# labwiz-module_t420.net
KiCad netlist of a schematic drawn in EAGLE
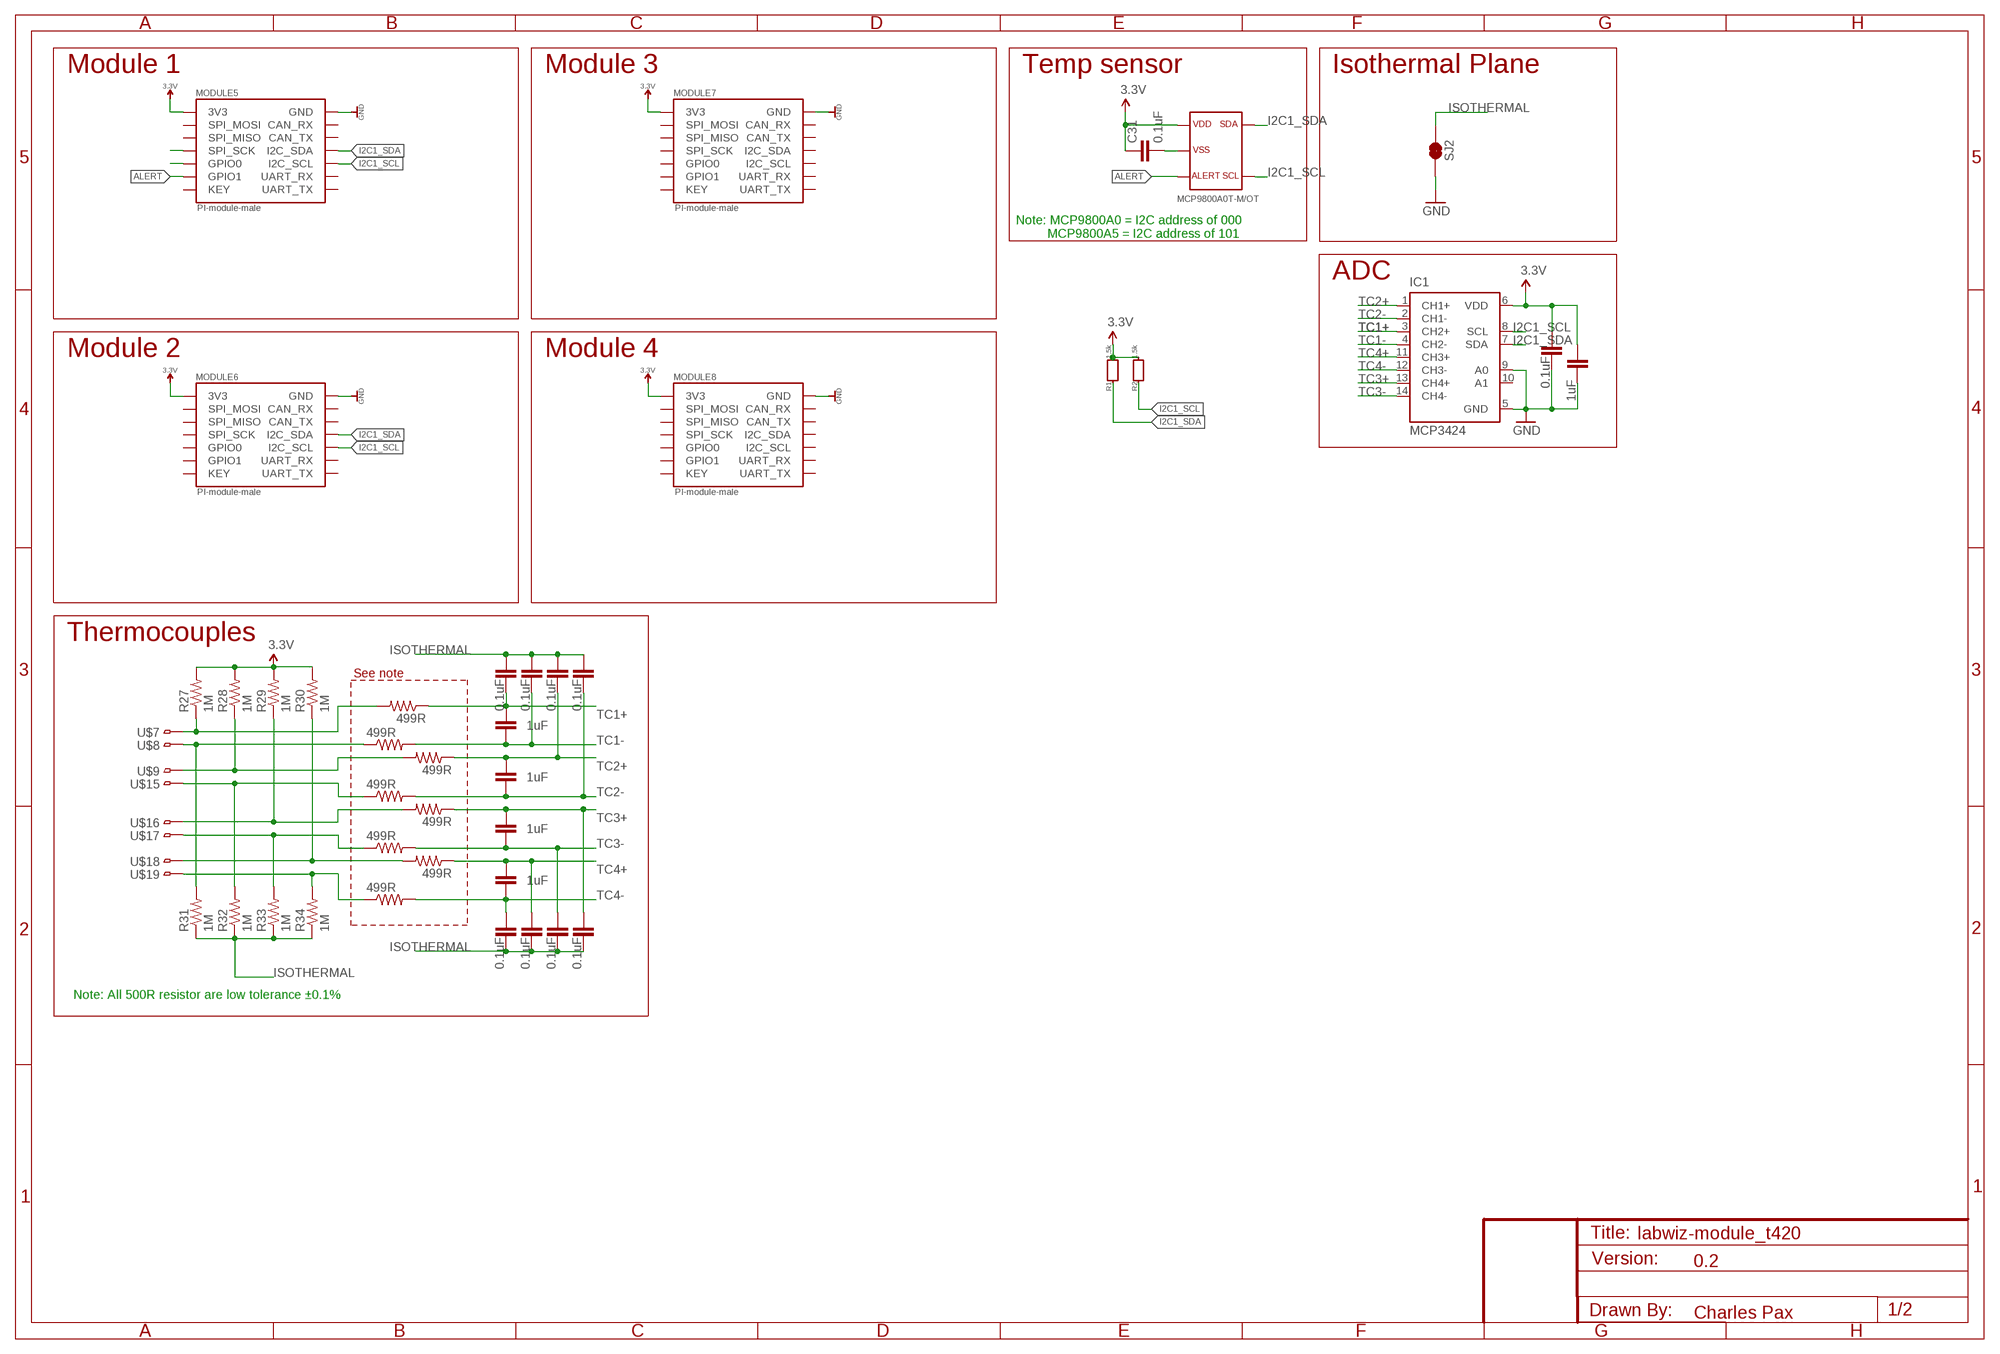
[diagram p0: schematic, sheet 1]

(export (version "E")
  (design (tool "Eeschema 10.0.6"))
  (components
    (comp (ref "C7")
      (value "1uF")
      (footprint "eagle-import:SPARKFUN-CAPACITORS_0603-CAP")
      (libsource (lib "eagle-import") (part "SPARKFUN-CAPACITORS_CAP0603-CAP"))
    )
    (comp (ref "C8")
      (value "1uF")
      (footprint "eagle-import:SPARKFUN-CAPACITORS_0603-CAP")
      (libsource (lib "eagle-import") (part "SPARKFUN-CAPACITORS_CAP0603-CAP"))
    )
    (comp (ref "C10")
      (value "1uF")
      (footprint "eagle-import:SPARKFUN-CAPACITORS_0603-CAP")
      (libsource (lib "eagle-import") (part "SPARKFUN-CAPACITORS_CAP0603-CAP"))
    )
    (comp (ref "C11")
      (value "1uF")
      (footprint "eagle-import:SPARKFUN-CAPACITORS_0603-CAP")
      (libsource (lib "eagle-import") (part "SPARKFUN-CAPACITORS_CAP0603-CAP"))
    )
    (comp (ref "C13")
      (value "0.1uF")
      (footprint "eagle-import:SPARKFUN-CAPACITORS_0603-CAP")
      (libsource (lib "eagle-import") (part "SPARKFUN-CAPACITORS_CAP0603-CAP"))
    )
    (comp (ref "C14")
      (value "0.1uF")
      (footprint "eagle-import:SPARKFUN-CAPACITORS_0603-CAP")
      (libsource (lib "eagle-import") (part "SPARKFUN-CAPACITORS_CAP0603-CAP"))
    )
    (comp (ref "C15")
      (value "0.1uF")
      (footprint "eagle-import:SPARKFUN-CAPACITORS_0603-CAP")
      (libsource (lib "eagle-import") (part "SPARKFUN-CAPACITORS_CAP0603-CAP"))
    )
    (comp (ref "C16")
      (value "0.1uF")
      (footprint "eagle-import:SPARKFUN-CAPACITORS_0603-CAP")
      (libsource (lib "eagle-import") (part "SPARKFUN-CAPACITORS_CAP0603-CAP"))
    )
    (comp (ref "C17")
      (value "0.1uF")
      (footprint "eagle-import:SPARKFUN-CAPACITORS_0603-CAP")
      (libsource (lib "eagle-import") (part "SPARKFUN-CAPACITORS_CAP0603-CAP"))
    )
    (comp (ref "C24")
      (value "0.1uF")
      (footprint "eagle-import:SPARKFUN-CAPACITORS_0603-CAP")
      (libsource (lib "eagle-import") (part "SPARKFUN-CAPACITORS_CAP0603-CAP"))
    )
    (comp (ref "C25")
      (value "0.1uF")
      (footprint "eagle-import:SPARKFUN-CAPACITORS_0603-CAP")
      (libsource (lib "eagle-import") (part "SPARKFUN-CAPACITORS_CAP0603-CAP"))
    )
    (comp (ref "C29")
      (value "0.1uF")
      (footprint "eagle-import:SPARKFUN-CAPACITORS_0603-CAP")
      (libsource (lib "eagle-import") (part "SPARKFUN-CAPACITORS_CAP0603-CAP"))
    )
    (comp (ref "C30")
      (value "1uF")
      (footprint "eagle-import:SPARKFUN-CAPACITORS_0603-CAP")
      (libsource (lib "eagle-import") (part "SPARKFUN-CAPACITORS_CAP0603-CAP"))
    )
    (comp (ref "C31")
      (value "0.1uF")
      (footprint "eagle-import:SPARKFUN-CAPACITORS_0603-CAP")
      (libsource (lib "eagle-import") (part "SPARKFUN-CAPACITORS_CAP0603-CAP"))
    )
    (comp (ref "C37")
      (value "0.1uF")
      (footprint "eagle-import:SPARKFUN-CAPACITORS_0603-CAP")
      (libsource (lib "eagle-import") (part "SPARKFUN-CAPACITORS_CAP0603-CAP"))
    )
    (comp (ref "IC1")
      (value "MCP3424")
      (footprint "eagle-import:SO14")
      (fields (field (name "MF") "Microchip Technology") (field (name "MPN") "MCP3424-E/SL"))
      (libsource (lib "eagle-import") (part "MCP3424"))
    )
    (comp (ref "MODULE5")
      (value "PI-module-male")
      (footprint "eagle-import:M07X2_2MM_EDGE")
      (fields (field (name "MF") "Pax Instruments") (field (name "MPN") "PIxxxx"))
      (libsource (lib "eagle-import") (part "PAX_MODULE_EDGE_MALE_MODULE"))
    )
    (comp (ref "MODULE6")
      (value "PI-module-male")
      (footprint "eagle-import:M07X2_2MM_EDGE")
      (fields (field (name "MF") "Pax Instruments") (field (name "MPN") "PIxxxx"))
      (libsource (lib "eagle-import") (part "PAX_MODULE_EDGE_MALE_MODULE"))
    )
    (comp (ref "MODULE7")
      (value "PI-module-male")
      (footprint "eagle-import:M07X2_2MM_EDGE")
      (fields (field (name "MF") "Pax Instruments") (field (name "MPN") "PIxxxx"))
      (libsource (lib "eagle-import") (part "PAX_MODULE_EDGE_MALE_MODULE"))
    )
    (comp (ref "MODULE8")
      (value "PI-module-male")
      (footprint "eagle-import:M07X2_2MM_EDGE")
      (fields (field (name "MF") "Pax Instruments") (field (name "MPN") "PIxxxx"))
      (libsource (lib "eagle-import") (part "PAX_MODULE_EDGE_MALE_MODULE"))
    )
    (comp (ref "R1")
      (value "1.5k")
      (footprint "eagle-import:0402")
      (libsource (lib "eagle-import") (part "R0402"))
    )
    (comp (ref "R2")
      (value "1.5k")
      (footprint "eagle-import:0402")
      (libsource (lib "eagle-import") (part "R0402"))
    )
    (comp (ref "R27")
      (value "1M")
      (footprint "eagle-import:SPARKFUN-RESISTORS_0603-RES")
      (libsource (lib "eagle-import") (part "SPARKFUN-RESISTORS_RESISTOR0603-RES"))
    )
    (comp (ref "R28")
      (value "1M")
      (footprint "eagle-import:SPARKFUN-RESISTORS_0603-RES")
      (libsource (lib "eagle-import") (part "SPARKFUN-RESISTORS_RESISTOR0603-RES"))
    )
    (comp (ref "R29")
      (value "1M")
      (footprint "eagle-import:SPARKFUN-RESISTORS_0603-RES")
      (libsource (lib "eagle-import") (part "SPARKFUN-RESISTORS_RESISTOR0603-RES"))
    )
    (comp (ref "R30")
      (value "1M")
      (footprint "eagle-import:SPARKFUN-RESISTORS_0603-RES")
      (libsource (lib "eagle-import") (part "SPARKFUN-RESISTORS_RESISTOR0603-RES"))
    )
    (comp (ref "R31")
      (value "1M")
      (footprint "eagle-import:SPARKFUN-RESISTORS_0603-RES")
      (libsource (lib "eagle-import") (part "SPARKFUN-RESISTORS_RESISTOR0603-RES"))
    )
    (comp (ref "R32")
      (value "1M")
      (footprint "eagle-import:SPARKFUN-RESISTORS_0603-RES")
      (libsource (lib "eagle-import") (part "SPARKFUN-RESISTORS_RESISTOR0603-RES"))
    )
    (comp (ref "R33")
      (value "1M")
      (footprint "eagle-import:SPARKFUN-RESISTORS_0603-RES")
      (libsource (lib "eagle-import") (part "SPARKFUN-RESISTORS_RESISTOR0603-RES"))
    )
    (comp (ref "R34")
      (value "1M")
      (footprint "eagle-import:SPARKFUN-RESISTORS_0603-RES")
      (libsource (lib "eagle-import") (part "SPARKFUN-RESISTORS_RESISTOR0603-RES"))
    )
    (comp (ref "R35")
      (value "499R")
      (footprint "eagle-import:SPARKFUN-RESISTORS_0603-RES")
      (fields (field (name "MF") "Vishay") (field (name "MPN") "TNPW0603499RBEEA"))
      (libsource (lib "eagle-import") (part "SPARKFUN-RESISTORS_RESISTOR0603-RES"))
    )
    (comp (ref "R36")
      (value "499R")
      (footprint "eagle-import:SPARKFUN-RESISTORS_0603-RES")
      (fields (field (name "MF") "Vishay") (field (name "MPN") "TNPW0603499RBEEA"))
      (libsource (lib "eagle-import") (part "SPARKFUN-RESISTORS_RESISTOR0603-RES"))
    )
    (comp (ref "R37")
      (value "499R")
      (footprint "eagle-import:SPARKFUN-RESISTORS_0603-RES")
      (fields (field (name "MF") "Vishay") (field (name "MPN") "TNPW0603499RBEEA"))
      (libsource (lib "eagle-import") (part "SPARKFUN-RESISTORS_RESISTOR0603-RES"))
    )
    (comp (ref "R38")
      (value "499R")
      (footprint "eagle-import:SPARKFUN-RESISTORS_0603-RES")
      (fields (field (name "MF") "Vishay") (field (name "MPN") "TNPW0603499RBEEA"))
      (libsource (lib "eagle-import") (part "SPARKFUN-RESISTORS_RESISTOR0603-RES"))
    )
    (comp (ref "R39")
      (value "499R")
      (footprint "eagle-import:SPARKFUN-RESISTORS_0603-RES")
      (fields (field (name "MF") "Vishay") (field (name "MPN") "TNPW0603499RBEEA"))
      (libsource (lib "eagle-import") (part "SPARKFUN-RESISTORS_RESISTOR0603-RES"))
    )
    (comp (ref "R40")
      (value "499R")
      (footprint "eagle-import:SPARKFUN-RESISTORS_0603-RES")
      (fields (field (name "MF") "Vishay") (field (name "MPN") "TNPW0603499RBEEA"))
      (libsource (lib "eagle-import") (part "SPARKFUN-RESISTORS_RESISTOR0603-RES"))
    )
    (comp (ref "R41")
      (value "499R")
      (footprint "eagle-import:SPARKFUN-RESISTORS_0603-RES")
      (fields (field (name "MF") "Vishay") (field (name "MPN") "TNPW0603499RBEEA"))
      (libsource (lib "eagle-import") (part "SPARKFUN-RESISTORS_RESISTOR0603-RES"))
    )
    (comp (ref "R42")
      (value "499R")
      (footprint "eagle-import:SPARKFUN-RESISTORS_0603-RES")
      (fields (field (name "MF") "Vishay") (field (name "MPN") "TNPW0603499RBEEA"))
      (libsource (lib "eagle-import") (part "SPARKFUN-RESISTORS_RESISTOR0603-RES"))
    )
    (comp (ref "SJ2")
      (value "JUMPER-PAD-2-NC_BY_TRACE")
      (footprint "eagle-import:PAD-JUMPER-2-NC_BY_TRACE_YES_SILK")
      (libsource (lib "eagle-import") (part "JUMPER-PAD-2-NC_BY_TRACE"))
    )
    (comp (ref "U$7")
      (value "TC-MINI-SINGLE")
      (footprint "eagle-import:TC-CLIP-SINGLE")
      (fields (field (name "MF") "Pax Instrument") (field (name "MPN") "Thermo-clip2"))
      (libsource (lib "eagle-import") (part "TC-MINI-SINGLE"))
    )
    (comp (ref "U$8")
      (value "TC-MINI-SINGLE")
      (footprint "eagle-import:TC-CLIP-SINGLE")
      (fields (field (name "MF") "Pax Instrument") (field (name "MPN") "Thermo-clip2"))
      (libsource (lib "eagle-import") (part "TC-MINI-SINGLE"))
    )
    (comp (ref "U$9")
      (value "TC-MINI-SINGLE")
      (footprint "eagle-import:TC-CLIP-SINGLE")
      (fields (field (name "MF") "Pax Instrument") (field (name "MPN") "Thermo-clip2"))
      (libsource (lib "eagle-import") (part "TC-MINI-SINGLE"))
    )
    (comp (ref "U$15")
      (value "TC-MINI-SINGLE")
      (footprint "eagle-import:TC-CLIP-SINGLE")
      (fields (field (name "MF") "Pax Instrument") (field (name "MPN") "Thermo-clip2"))
      (libsource (lib "eagle-import") (part "TC-MINI-SINGLE"))
    )
    (comp (ref "U$16")
      (value "TC-MINI-SINGLE")
      (footprint "eagle-import:TC-CLIP-SINGLE")
      (fields (field (name "MF") "Pax Instrument") (field (name "MPN") "Thermo-clip2"))
      (libsource (lib "eagle-import") (part "TC-MINI-SINGLE"))
    )
    (comp (ref "U$17")
      (value "TC-MINI-SINGLE")
      (footprint "eagle-import:TC-CLIP-SINGLE")
      (fields (field (name "MF") "Pax Instrument") (field (name "MPN") "Thermo-clip2"))
      (libsource (lib "eagle-import") (part "TC-MINI-SINGLE"))
    )
    (comp (ref "U$18")
      (value "TC-MINI-SINGLE")
      (footprint "eagle-import:TC-CLIP-SINGLE")
      (fields (field (name "MF") "Pax Instrument") (field (name "MPN") "Thermo-clip2"))
      (libsource (lib "eagle-import") (part "TC-MINI-SINGLE"))
    )
    (comp (ref "U$19")
      (value "TC-MINI-SINGLE")
      (footprint "eagle-import:TC-CLIP-SINGLE")
      (fields (field (name "MF") "Pax Instrument") (field (name "MPN") "Thermo-clip2"))
      (libsource (lib "eagle-import") (part "TC-MINI-SINGLE"))
    )
    (comp (ref "U1")
      (value "MCP9800")
      (footprint "eagle-import:SOT23-5L")
      (fields (field (name "MF") "Microchip Technology") (field (name "MPN") "MCP9800A0T-M/OT"))
      (libsource (lib "eagle-import") (part "MCP9800"))
    )
  )
  (nets
    (net (code "1") (name "3.3V") (class "Default")
      (node (ref "C29") (pin "1") (pinfunction "1_1") (pintype "passive"))
      (node (ref "C30") (pin "1") (pinfunction "1_1") (pintype "passive"))
      (node (ref "C31") (pin "1") (pinfunction "1_1") (pintype "passive"))
      (node (ref "IC1") (pin "6") (pinfunction "VDD_6") (pintype "power_in"))
      (node (ref "MODULE5") (pin "P$13") (pinfunction "3V3_P$13") (pintype "power_in"))
      (node (ref "MODULE6") (pin "P$13") (pinfunction "3V3_P$13") (pintype "power_in"))
      (node (ref "MODULE7") (pin "P$13") (pinfunction "3V3_P$13") (pintype "power_in"))
      (node (ref "MODULE8") (pin "P$13") (pinfunction "3V3_P$13") (pintype "power_in"))
      (node (ref "R1") (pin "1") (pinfunction "1_1") (pintype "passive"))
      (node (ref "R2") (pin "1") (pinfunction "1_1") (pintype "passive"))
      (node (ref "R27") (pin "2") (pinfunction "2_2") (pintype "passive"))
      (node (ref "R28") (pin "2") (pinfunction "2_2") (pintype "passive"))
      (node (ref "R29") (pin "2") (pinfunction "2_2") (pintype "passive"))
      (node (ref "R30") (pin "2") (pinfunction "2_2") (pintype "passive"))
      (node (ref "U1") (pin "1") (pinfunction "1_1") (pintype "bidirectional"))
    )
    (net (code "2") (name "ALERT") (class "Default")
      (node (ref "MODULE5") (pin "P$3") (pinfunction "GPIO1_P$3") (pintype "bidirectional"))
      (node (ref "U1") (pin "3") (pinfunction "3_3") (pintype "bidirectional"))
    )
    (net (code "3") (name "GND") (class "Default")
      (node (ref "C29") (pin "2") (pinfunction "2_2") (pintype "passive"))
      (node (ref "C30") (pin "2") (pinfunction "2_2") (pintype "passive"))
      (node (ref "IC1") (pin "5") (pinfunction "GND_5") (pintype "power_in"))
      (node (ref "IC1") (pin "9") (pinfunction "A0_9") (pintype "input"))
      (node (ref "MODULE5") (pin "P$14") (pinfunction "GND_P$14") (pintype "power_in"))
      (node (ref "MODULE6") (pin "P$14") (pinfunction "GND_P$14") (pintype "power_in"))
      (node (ref "MODULE7") (pin "P$14") (pinfunction "GND_P$14") (pintype "power_in"))
      (node (ref "MODULE8") (pin "P$14") (pinfunction "GND_P$14") (pintype "power_in"))
      (node (ref "SJ2") (pin "1") (pinfunction "1_1") (pintype "passive"))
    )
    (net (code "4") (name "I2C1_SCL") (class "Default")
      (node (ref "IC1") (pin "8") (pinfunction "SCL_8") (pintype "input"))
      (node (ref "MODULE5") (pin "P$6") (pinfunction "I2C_SCL_P$6") (pintype "bidirectional"))
      (node (ref "MODULE6") (pin "P$6") (pinfunction "I2C_SCL_P$6") (pintype "bidirectional"))
      (node (ref "R2") (pin "2") (pinfunction "2_2") (pintype "passive"))
      (node (ref "U1") (pin "4") (pinfunction "4_4") (pintype "bidirectional"))
    )
    (net (code "5") (name "I2C1_SDA") (class "Default")
      (node (ref "IC1") (pin "7") (pinfunction "SDA_7") (pintype "bidirectional"))
      (node (ref "MODULE5") (pin "P$8") (pinfunction "I2C_SDA_P$8") (pintype "bidirectional"))
      (node (ref "MODULE6") (pin "P$8") (pinfunction "I2C_SDA_P$8") (pintype "bidirectional"))
      (node (ref "R1") (pin "2") (pinfunction "2_2") (pintype "passive"))
      (node (ref "U1") (pin "5") (pinfunction "5_5") (pintype "bidirectional"))
    )
    (net (code "6") (name "ISOTHERMAL") (class "Default")
      (node (ref "C13") (pin "2") (pinfunction "2_2") (pintype "passive"))
      (node (ref "C14") (pin "2") (pinfunction "2_2") (pintype "passive"))
      (node (ref "C15") (pin "2") (pinfunction "2_2") (pintype "passive"))
      (node (ref "C16") (pin "2") (pinfunction "2_2") (pintype "passive"))
      (node (ref "C17") (pin "1") (pinfunction "1_1") (pintype "passive"))
      (node (ref "C24") (pin "1") (pinfunction "1_1") (pintype "passive"))
      (node (ref "C25") (pin "1") (pinfunction "1_1") (pintype "passive"))
      (node (ref "C31") (pin "2") (pinfunction "2_2") (pintype "passive"))
      (node (ref "C37") (pin "1") (pinfunction "1_1") (pintype "passive"))
      (node (ref "R31") (pin "1") (pinfunction "1_1") (pintype "passive"))
      (node (ref "R32") (pin "1") (pinfunction "1_1") (pintype "passive"))
      (node (ref "R33") (pin "1") (pinfunction "1_1") (pintype "passive"))
      (node (ref "R34") (pin "1") (pinfunction "1_1") (pintype "passive"))
      (node (ref "SJ2") (pin "2") (pinfunction "2_2") (pintype "passive"))
      (node (ref "U1") (pin "2") (pinfunction "2_2") (pintype "bidirectional"))
    )
    (net (code "7") (name "Net-(U$7-1)") (class "Default")
      (node (ref "R27") (pin "1") (pinfunction "1_1") (pintype "passive"))
      (node (ref "R35") (pin "2") (pinfunction "2_2") (pintype "passive"))
      (node (ref "U$7") (pin "P$1") (pinfunction "1_P$1") (pintype "passive"))
    )
    (net (code "8") (name "Net-(U$8-1)") (class "Default")
      (node (ref "R31") (pin "2") (pinfunction "2_2") (pintype "passive"))
      (node (ref "R36") (pin "1") (pinfunction "1_1") (pintype "passive"))
      (node (ref "U$8") (pin "P$1") (pinfunction "1_P$1") (pintype "passive"))
    )
    (net (code "9") (name "Net-(U$9-1)") (class "Default")
      (node (ref "R28") (pin "1") (pinfunction "1_1") (pintype "passive"))
      (node (ref "R37") (pin "2") (pinfunction "2_2") (pintype "passive"))
      (node (ref "U$9") (pin "P$1") (pinfunction "1_P$1") (pintype "passive"))
    )
    (net (code "10") (name "Net-(U$15-1)") (class "Default")
      (node (ref "R32") (pin "2") (pinfunction "2_2") (pintype "passive"))
      (node (ref "R38") (pin "1") (pinfunction "1_1") (pintype "passive"))
      (node (ref "U$15") (pin "P$1") (pinfunction "1_P$1") (pintype "passive"))
    )
    (net (code "11") (name "Net-(U$16-1)") (class "Default")
      (node (ref "R29") (pin "1") (pinfunction "1_1") (pintype "passive"))
      (node (ref "R39") (pin "2") (pinfunction "2_2") (pintype "passive"))
      (node (ref "U$16") (pin "P$1") (pinfunction "1_P$1") (pintype "passive"))
    )
    (net (code "12") (name "Net-(U$17-1)") (class "Default")
      (node (ref "R33") (pin "2") (pinfunction "2_2") (pintype "passive"))
      (node (ref "R41") (pin "1") (pinfunction "1_1") (pintype "passive"))
      (node (ref "U$17") (pin "P$1") (pinfunction "1_P$1") (pintype "passive"))
    )
    (net (code "13") (name "Net-(U$18-1)") (class "Default")
      (node (ref "R30") (pin "1") (pinfunction "1_1") (pintype "passive"))
      (node (ref "R40") (pin "2") (pinfunction "2_2") (pintype "passive"))
      (node (ref "U$18") (pin "P$1") (pinfunction "1_P$1") (pintype "passive"))
    )
    (net (code "14") (name "Net-(U$19-1)") (class "Default")
      (node (ref "R34") (pin "2") (pinfunction "2_2") (pintype "passive"))
      (node (ref "R42") (pin "1") (pinfunction "1_1") (pintype "passive"))
      (node (ref "U$19") (pin "P$1") (pinfunction "1_P$1") (pintype "passive"))
    )
    (net (code "15") (name "TC1+") (class "Default")
      (node (ref "C17") (pin "2") (pinfunction "2_2") (pintype "passive"))
      (node (ref "C7") (pin "1") (pinfunction "1_1") (pintype "passive"))
      (node (ref "IC1") (pin "3") (pinfunction "CH2+_3") (pintype "input"))
      (node (ref "R35") (pin "1") (pinfunction "1_1") (pintype "passive"))
    )
    (net (code "16") (name "TC1-") (class "Default")
      (node (ref "C24") (pin "2") (pinfunction "2_2") (pintype "passive"))
      (node (ref "C7") (pin "2") (pinfunction "2_2") (pintype "passive"))
      (node (ref "IC1") (pin "4") (pinfunction "CH2-_4") (pintype "input"))
      (node (ref "R36") (pin "2") (pinfunction "2_2") (pintype "passive"))
    )
    (net (code "17") (name "TC2+") (class "Default")
      (node (ref "C25") (pin "2") (pinfunction "2_2") (pintype "passive"))
      (node (ref "C8") (pin "1") (pinfunction "1_1") (pintype "passive"))
      (node (ref "IC1") (pin "1") (pinfunction "CH1+_1") (pintype "input"))
      (node (ref "R37") (pin "1") (pinfunction "1_1") (pintype "passive"))
    )
    (net (code "18") (name "TC2-") (class "Default")
      (node (ref "C37") (pin "2") (pinfunction "2_2") (pintype "passive"))
      (node (ref "C8") (pin "2") (pinfunction "2_2") (pintype "passive"))
      (node (ref "IC1") (pin "2") (pinfunction "CH1-_2") (pintype "input"))
      (node (ref "R38") (pin "2") (pinfunction "2_2") (pintype "passive"))
    )
    (net (code "19") (name "TC3+") (class "Default")
      (node (ref "C10") (pin "1") (pinfunction "1_1") (pintype "passive"))
      (node (ref "C16") (pin "1") (pinfunction "1_1") (pintype "passive"))
      (node (ref "IC1") (pin "13") (pinfunction "CH4+_13") (pintype "input"))
      (node (ref "R39") (pin "1") (pinfunction "1_1") (pintype "passive"))
    )
    (net (code "20") (name "TC3-") (class "Default")
      (node (ref "C10") (pin "2") (pinfunction "2_2") (pintype "passive"))
      (node (ref "C15") (pin "1") (pinfunction "1_1") (pintype "passive"))
      (node (ref "IC1") (pin "14") (pinfunction "CH4-_14") (pintype "input"))
      (node (ref "R41") (pin "2") (pinfunction "2_2") (pintype "passive"))
    )
    (net (code "21") (name "TC4+") (class "Default")
      (node (ref "C11") (pin "1") (pinfunction "1_1") (pintype "passive"))
      (node (ref "C14") (pin "1") (pinfunction "1_1") (pintype "passive"))
      (node (ref "IC1") (pin "11") (pinfunction "CH3+_11") (pintype "input"))
      (node (ref "R40") (pin "1") (pinfunction "1_1") (pintype "passive"))
    )
    (net (code "22") (name "TC4-") (class "Default")
      (node (ref "C11") (pin "2") (pinfunction "2_2") (pintype "passive"))
      (node (ref "C13") (pin "1") (pinfunction "1_1") (pintype "passive"))
      (node (ref "IC1") (pin "12") (pinfunction "CH3-_12") (pintype "input"))
      (node (ref "R42") (pin "2") (pinfunction "2_2") (pintype "passive"))
    )
    (net (code "23") (name "unconnected-(IC1-A1-Pad10)") (class "Default")
      (node (ref "IC1") (pin "10") (pinfunction "A1_10") (pintype "input"))
    )
    (net (code "24") (name "unconnected-(MODULE5-CAN_RX-PadP$12)") (class "Default")
      (node (ref "MODULE5") (pin "P$12") (pinfunction "CAN_RX_P$12") (pintype "bidirectional"))
    )
    (net (code "25") (name "unconnected-(MODULE5-CAN_TX-PadP$10)") (class "Default")
      (node (ref "MODULE5") (pin "P$10") (pinfunction "CAN_TX_P$10") (pintype "bidirectional"))
    )
    (net (code "26") (name "unconnected-(MODULE5-GPIO0-PadP$5)") (class "Default")
      (node (ref "MODULE5") (pin "P$5") (pinfunction "GPIO0_P$5") (pintype "bidirectional"))
    )
    (net (code "27") (name "unconnected-(MODULE5-KEY-PadP$1)") (class "Default")
      (node (ref "MODULE5") (pin "P$1") (pinfunction "KEY_P$1") (pintype "no_connect"))
    )
    (net (code "28") (name "unconnected-(MODULE5-SPI_MISO-PadP$9)") (class "Default")
      (node (ref "MODULE5") (pin "P$9") (pinfunction "SPI_MISO_P$9") (pintype "bidirectional"))
    )
    (net (code "29") (name "unconnected-(MODULE5-SPI_MOSI-PadP$11)") (class "Default")
      (node (ref "MODULE5") (pin "P$11") (pinfunction "SPI_MOSI_P$11") (pintype "bidirectional"))
    )
    (net (code "30") (name "unconnected-(MODULE5-SPI_SCK-PadP$7)") (class "Default")
      (node (ref "MODULE5") (pin "P$7") (pinfunction "SPI_SCK_P$7") (pintype "bidirectional"))
    )
    (net (code "31") (name "unconnected-(MODULE5-UART_RX-PadP$4)") (class "Default")
      (node (ref "MODULE5") (pin "P$4") (pinfunction "UART_RX_P$4") (pintype "bidirectional"))
    )
    (net (code "32") (name "unconnected-(MODULE5-UART_TX-PadP$2)") (class "Default")
      (node (ref "MODULE5") (pin "P$2") (pinfunction "UART_TX_P$2") (pintype "bidirectional"))
    )
    (net (code "33") (name "unconnected-(MODULE6-CAN_RX-PadP$12)") (class "Default")
      (node (ref "MODULE6") (pin "P$12") (pinfunction "CAN_RX_P$12") (pintype "bidirectional"))
    )
    (net (code "34") (name "unconnected-(MODULE6-CAN_TX-PadP$10)") (class "Default")
      (node (ref "MODULE6") (pin "P$10") (pinfunction "CAN_TX_P$10") (pintype "bidirectional"))
    )
    (net (code "35") (name "unconnected-(MODULE6-GPIO0-PadP$5)") (class "Default")
      (node (ref "MODULE6") (pin "P$5") (pinfunction "GPIO0_P$5") (pintype "bidirectional"))
    )
    (net (code "36") (name "unconnected-(MODULE6-GPIO1-PadP$3)") (class "Default")
      (node (ref "MODULE6") (pin "P$3") (pinfunction "GPIO1_P$3") (pintype "bidirectional"))
    )
    (net (code "37") (name "unconnected-(MODULE6-KEY-PadP$1)") (class "Default")
      (node (ref "MODULE6") (pin "P$1") (pinfunction "KEY_P$1") (pintype "no_connect"))
    )
    (net (code "38") (name "unconnected-(MODULE6-SPI_MISO-PadP$9)") (class "Default")
      (node (ref "MODULE6") (pin "P$9") (pinfunction "SPI_MISO_P$9") (pintype "bidirectional"))
    )
    (net (code "39") (name "unconnected-(MODULE6-SPI_MOSI-PadP$11)") (class "Default")
      (node (ref "MODULE6") (pin "P$11") (pinfunction "SPI_MOSI_P$11") (pintype "bidirectional"))
    )
    (net (code "40") (name "unconnected-(MODULE6-SPI_SCK-PadP$7)") (class "Default")
      (node (ref "MODULE6") (pin "P$7") (pinfunction "SPI_SCK_P$7") (pintype "bidirectional"))
    )
    (net (code "41") (name "unconnected-(MODULE6-UART_RX-PadP$4)") (class "Default")
      (node (ref "MODULE6") (pin "P$4") (pinfunction "UART_RX_P$4") (pintype "bidirectional"))
    )
    (net (code "42") (name "unconnected-(MODULE6-UART_TX-PadP$2)") (class "Default")
      (node (ref "MODULE6") (pin "P$2") (pinfunction "UART_TX_P$2") (pintype "bidirectional"))
    )
    (net (code "43") (name "unconnected-(MODULE7-CAN_RX-PadP$12)") (class "Default")
      (node (ref "MODULE7") (pin "P$12") (pinfunction "CAN_RX_P$12") (pintype "bidirectional"))
    )
    (net (code "44") (name "unconnected-(MODULE7-CAN_TX-PadP$10)") (class "Default")
      (node (ref "MODULE7") (pin "P$10") (pinfunction "CAN_TX_P$10") (pintype "bidirectional"))
    )
    (net (code "45") (name "unconnected-(MODULE7-GPIO0-PadP$5)") (class "Default")
      (node (ref "MODULE7") (pin "P$5") (pinfunction "GPIO0_P$5") (pintype "bidirectional"))
    )
    (net (code "46") (name "unconnected-(MODULE7-GPIO1-PadP$3)") (class "Default")
      (node (ref "MODULE7") (pin "P$3") (pinfunction "GPIO1_P$3") (pintype "bidirectional"))
    )
    (net (code "47") (name "unconnected-(MODULE7-I2C_SCL-PadP$6)") (class "Default")
      (node (ref "MODULE7") (pin "P$6") (pinfunction "I2C_SCL_P$6") (pintype "bidirectional"))
    )
    (net (code "48") (name "unconnected-(MODULE7-I2C_SDA-PadP$8)") (class "Default")
      (node (ref "MODULE7") (pin "P$8") (pinfunction "I2C_SDA_P$8") (pintype "bidirectional"))
    )
    (net (code "49") (name "unconnected-(MODULE7-KEY-PadP$1)") (class "Default")
      (node (ref "MODULE7") (pin "P$1") (pinfunction "KEY_P$1") (pintype "no_connect"))
    )
    (net (code "50") (name "unconnected-(MODULE7-SPI_MISO-PadP$9)") (class "Default")
      (node (ref "MODULE7") (pin "P$9") (pinfunction "SPI_MISO_P$9") (pintype "bidirectional"))
    )
    (net (code "51") (name "unconnected-(MODULE7-SPI_MOSI-PadP$11)") (class "Default")
      (node (ref "MODULE7") (pin "P$11") (pinfunction "SPI_MOSI_P$11") (pintype "bidirectional"))
    )
    (net (code "52") (name "unconnected-(MODULE7-SPI_SCK-PadP$7)") (class "Default")
      (node (ref "MODULE7") (pin "P$7") (pinfunction "SPI_SCK_P$7") (pintype "bidirectional"))
    )
    (net (code "53") (name "unconnected-(MODULE7-UART_RX-PadP$4)") (class "Default")
      (node (ref "MODULE7") (pin "P$4") (pinfunction "UART_RX_P$4") (pintype "bidirectional"))
    )
    (net (code "54") (name "unconnected-(MODULE7-UART_TX-PadP$2)") (class "Default")
      (node (ref "MODULE7") (pin "P$2") (pinfunction "UART_TX_P$2") (pintype "bidirectional"))
    )
    (net (code "55") (name "unconnected-(MODULE8-CAN_RX-PadP$12)") (class "Default")
      (node (ref "MODULE8") (pin "P$12") (pinfunction "CAN_RX_P$12") (pintype "bidirectional"))
    )
    (net (code "56") (name "unconnected-(MODULE8-CAN_TX-PadP$10)") (class "Default")
      (node (ref "MODULE8") (pin "P$10") (pinfunction "CAN_TX_P$10") (pintype "bidirectional"))
    )
    (net (code "57") (name "unconnected-(MODULE8-GPIO0-PadP$5)") (class "Default")
      (node (ref "MODULE8") (pin "P$5") (pinfunction "GPIO0_P$5") (pintype "bidirectional"))
    )
    (net (code "58") (name "unconnected-(MODULE8-GPIO1-PadP$3)") (class "Default")
      (node (ref "MODULE8") (pin "P$3") (pinfunction "GPIO1_P$3") (pintype "bidirectional"))
    )
    (net (code "59") (name "unconnected-(MODULE8-I2C_SCL-PadP$6)") (class "Default")
      (node (ref "MODULE8") (pin "P$6") (pinfunction "I2C_SCL_P$6") (pintype "bidirectional"))
    )
    (net (code "60") (name "unconnected-(MODULE8-I2C_SDA-PadP$8)") (class "Default")
      (node (ref "MODULE8") (pin "P$8") (pinfunction "I2C_SDA_P$8") (pintype "bidirectional"))
    )
    (net (code "61") (name "unconnected-(MODULE8-KEY-PadP$1)") (class "Default")
      (node (ref "MODULE8") (pin "P$1") (pinfunction "KEY_P$1") (pintype "no_connect"))
    )
    (net (code "62") (name "unconnected-(MODULE8-SPI_MISO-PadP$9)") (class "Default")
      (node (ref "MODULE8") (pin "P$9") (pinfunction "SPI_MISO_P$9") (pintype "bidirectional"))
    )
    (net (code "63") (name "unconnected-(MODULE8-SPI_MOSI-PadP$11)") (class "Default")
      (node (ref "MODULE8") (pin "P$11") (pinfunction "SPI_MOSI_P$11") (pintype "bidirectional"))
    )
    (net (code "64") (name "unconnected-(MODULE8-SPI_SCK-PadP$7)") (class "Default")
      (node (ref "MODULE8") (pin "P$7") (pinfunction "SPI_SCK_P$7") (pintype "bidirectional"))
    )
    (net (code "65") (name "unconnected-(MODULE8-UART_RX-PadP$4)") (class "Default")
      (node (ref "MODULE8") (pin "P$4") (pinfunction "UART_RX_P$4") (pintype "bidirectional"))
    )
    (net (code "66") (name "unconnected-(MODULE8-UART_TX-PadP$2)") (class "Default")
      (node (ref "MODULE8") (pin "P$2") (pinfunction "UART_TX_P$2") (pintype "bidirectional"))
    )
  )
)
